# 8_RJ45_Connector.net
KiCad netlist of a schematic drawn in Altium Designer
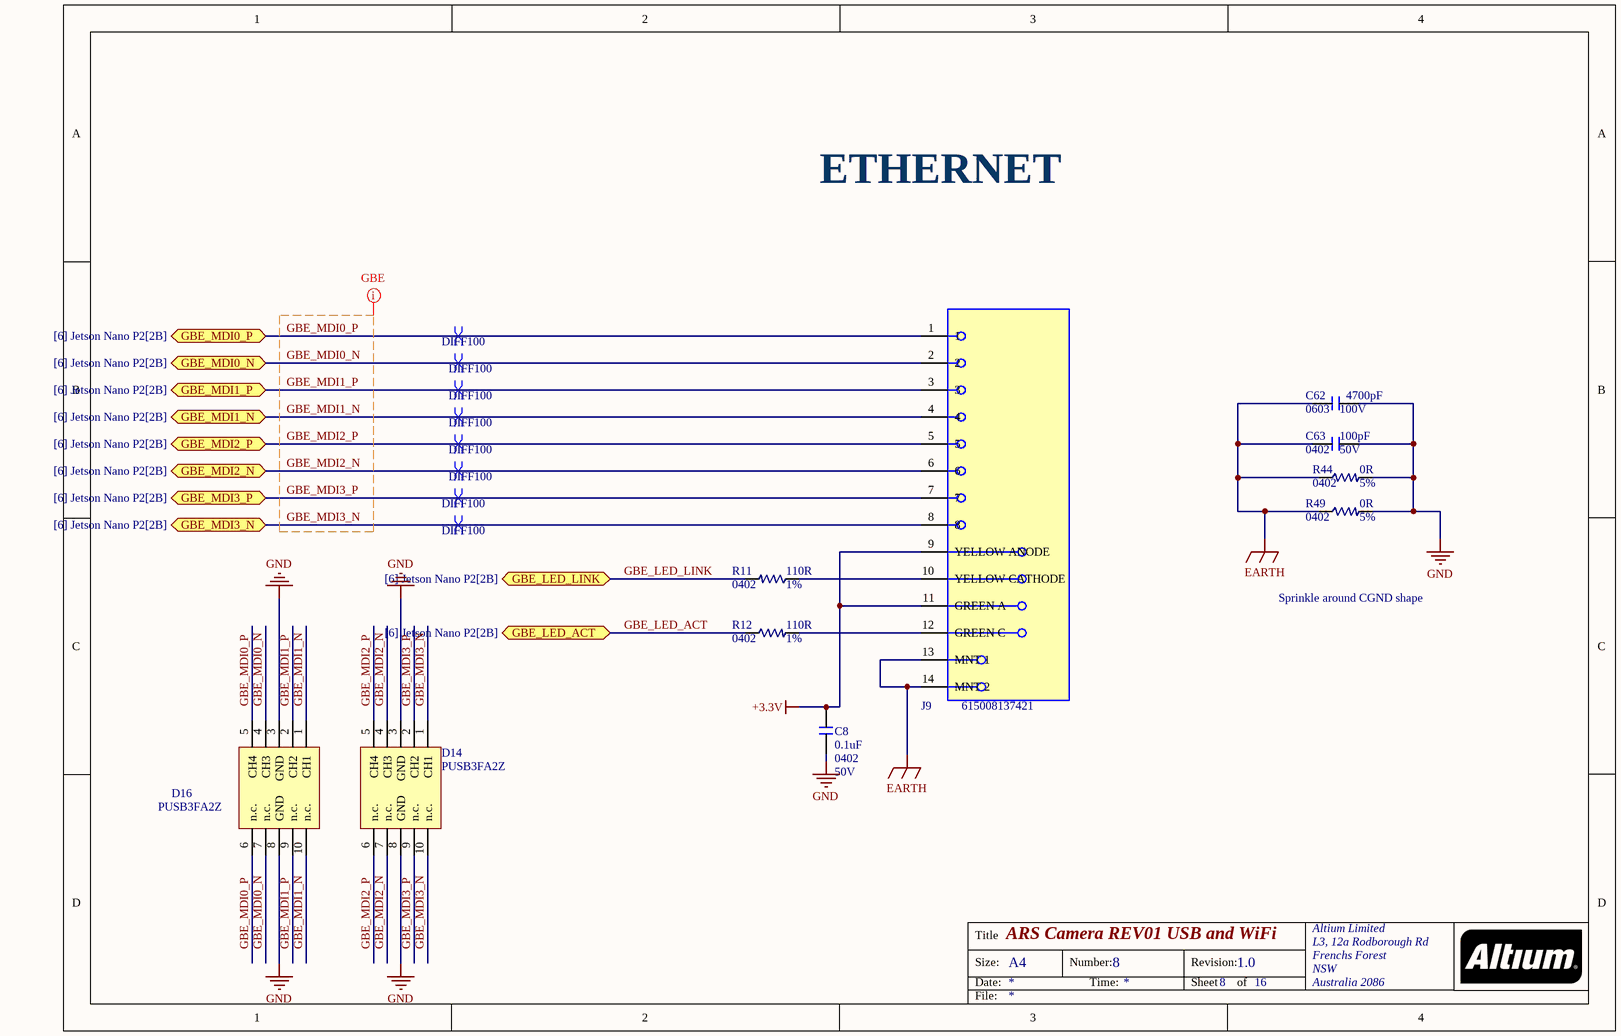
[diagram p0: [8] RJ45 Connector.SchDoc]

(export (version "E")
  (design (tool "Eeschema 10.0.6"))
  (components
    (comp (ref "C8")
      (value "0.1uF")
      (footprint "C0402M")
      (description "CAP CER 0.1UF 50V X7R 0402")
      (fields
        (field (name "MANUFACTURER") "Murata")
        (field (name "MANUFACTURER PART NUMBER") "GRM155R71H104KE14D")
        (field (name "CASE/PACKAGE") "0402")
        (field (name "VOLTAGE") "50V")
      )
      (libsource (lib "CommonLib") (part "CAP_CER"))
    )
    (comp (ref "C62")
      (value "4700pF")
      (footprint "C0603M")
      (description "CAP CER 4700PF 100V X7R 0603")
      (fields
        (field (name "CASE/PACKAGE") "0603")
        (field (name "TOLERANCE") "10%")
        (field (name "VOLTAGE RATING") "100V")
      )
      (libsource (lib "") (part "CAP_CER_1"))
    )
    (comp (ref "C63")
      (value "100pF")
      (footprint "C0402M")
      (description "CAP CER 100PF 50V C0G/NP0 0402")
      (fields
        (field (name "MANUFACTURER") "Murata")
        (field (name "MANUFACTURER PART NUMBER") "GRM1555C1H101JA01J")
        (field (name "CASE/PACKAGE") "0402")
        (field (name "VOLTAGE") "50V")
      )
      (libsource (lib "CommonLib") (part "CAP_CER"))
    )
    (comp (ref "D14")
      (value "PUSB3FA2Z")
      (footprint "SON50P100X50-10N")
      (description "ESD Suppressors / TVS Diodes PUSB3FA2 XSON10")
      (libsource (lib "Nauvus") (part "PUSB3FA2Z"))
    )
    (comp (ref "D16")
      (value "PUSB3FA2Z")
      (footprint "SON50P100X50-10N")
      (description "ESD Suppressors / TVS Diodes PUSB3FA2 XSON10")
      (libsource (lib "Nauvus") (part "PUSB3FA2Z"))
    )
    (comp (ref "J9")
      (value "615008137421")
      (footprint "Wurth_615008137421_MFG")
      (description "Modular Jack WR-MJ, Tab Up, Shielded, with LED and EMI Panel Finger, Horizontal Entry, THT, 8P8C")
      (libsource (lib "Schlib1") (part "615008137421"))
    )
    (comp (ref "R11")
      (value "110R")
      (footprint "R0402M")
      (description "RES SMD 110 OHM 1% 1/16W 0402")
      (fields (field (name "CASE CODE (IMPERIAL)") "0402") (field (name "TOLERANCE") "1%"))
      (libsource (lib "CommonLib") (part "RES_SMD"))
    )
    (comp (ref "R12")
      (value "110R")
      (footprint "R0402M")
      (description "RES SMD 110 OHM 1% 1/16W 0402")
      (fields (field (name "CASE CODE (IMPERIAL)") "0402") (field (name "TOLERANCE") "1%"))
      (libsource (lib "CommonLib") (part "RES_SMD"))
    )
    (comp (ref "R44")
      (value "0R")
      (footprint "R0402M")
      (description "YAGEO - RC0402JR-070RL. - RES, THICK FILM, 0R, 0.0625W, 0402")
      (fields
        (field (name "CASE/PACKAGE") "0402")
        (field (name "TOLERANCE") "5%")
        (field (name "RESISTANCE TOLERANCE") "5%")
      )
      (libsource (lib "CommonLib") (part "RES_SMD"))
    )
    (comp (ref "R49")
      (value "0R")
      (footprint "R0402M")
      (description "YAGEO - RC0402JR-070RL. - RES, THICK FILM, 0R, 0.0625W, 0402")
      (fields
        (field (name "CASE/PACKAGE") "0402")
        (field (name "TOLERANCE") "5%")
        (field (name "RESISTANCE TOLERANCE") "5%")
      )
      (libsource (lib "CommonLib") (part "RES_SMD"))
    )
  )
  (nets
    (net (code "1") (name "+3.3V") (class "Default")
      (node (ref "C8") (pin "2") (pinfunction "2_2") (pintype "passive"))
      (node (ref "J9") (pin "11") (pinfunction "GREEN_A_11") (pintype "passive"))
      (node (ref "J9") (pin "9") (pinfunction "YELLOW_ANODE_9") (pintype "passive"))
    )
    (net (code "2") (name "/GBE_LED_ACT") (class "Default")
      (node (ref "R12") (pin "2") (pinfunction "2_2") (pintype "passive"))
    )
    (net (code "3") (name "/GBE_LED_LINK") (class "Default")
      (node (ref "R11") (pin "1") (pinfunction "1_1") (pintype "passive"))
    )
    (net (code "4") (name "/GBE_MDI0_N") (class "Default")
      (node (ref "D16") (pin "4") (pinfunction "CH3_4") (pintype "passive"))
      (node (ref "D16") (pin "7") (pinfunction "n.c._7") (pintype "passive"))
      (node (ref "J9") (pin "2") (pinfunction "2_2") (pintype "passive"))
    )
    (net (code "5") (name "/GBE_MDI0_P") (class "Default")
      (node (ref "D16") (pin "5") (pinfunction "CH4_5") (pintype "passive"))
      (node (ref "D16") (pin "6") (pinfunction "n.c._6") (pintype "passive"))
      (node (ref "J9") (pin "1") (pinfunction "1_1") (pintype "passive"))
    )
    (net (code "6") (name "/GBE_MDI1_N") (class "Default")
      (node (ref "D16") (pin "1") (pinfunction "CH1_1") (pintype "passive"))
      (node (ref "D16") (pin "10") (pinfunction "n.c._10") (pintype "passive"))
      (node (ref "J9") (pin "4") (pinfunction "4_4") (pintype "passive"))
    )
    (net (code "7") (name "/GBE_MDI1_P") (class "Default")
      (node (ref "D16") (pin "2") (pinfunction "CH2_2") (pintype "passive"))
      (node (ref "D16") (pin "9") (pinfunction "n.c._9") (pintype "passive"))
      (node (ref "J9") (pin "3") (pinfunction "3_3") (pintype "passive"))
    )
    (net (code "8") (name "/GBE_MDI2_N") (class "Default")
      (node (ref "D14") (pin "4") (pinfunction "CH3_4") (pintype "passive"))
      (node (ref "D14") (pin "7") (pinfunction "n.c._7") (pintype "passive"))
      (node (ref "J9") (pin "6") (pinfunction "6_6") (pintype "passive"))
    )
    (net (code "9") (name "/GBE_MDI2_P") (class "Default")
      (node (ref "D14") (pin "5") (pinfunction "CH4_5") (pintype "passive"))
      (node (ref "D14") (pin "6") (pinfunction "n.c._6") (pintype "passive"))
      (node (ref "J9") (pin "5") (pinfunction "5_5") (pintype "passive"))
    )
    (net (code "10") (name "/GBE_MDI3_N") (class "Default")
      (node (ref "D14") (pin "1") (pinfunction "CH1_1") (pintype "passive"))
      (node (ref "D14") (pin "10") (pinfunction "n.c._10") (pintype "passive"))
      (node (ref "J9") (pin "8") (pinfunction "8_8") (pintype "passive"))
    )
    (net (code "11") (name "/GBE_MDI3_P") (class "Default")
      (node (ref "D14") (pin "2") (pinfunction "CH2_2") (pintype "passive"))
      (node (ref "D14") (pin "9") (pinfunction "n.c._9") (pintype "passive"))
      (node (ref "J9") (pin "7") (pinfunction "7_7") (pintype "passive"))
    )
    (net (code "12") (name "EARTH") (class "Default")
      (node (ref "C62") (pin "1") (pinfunction "1_1") (pintype "passive"))
      (node (ref "C63") (pin "2") (pinfunction "2_2") (pintype "passive"))
      (node (ref "J9") (pin "13") (pinfunction "MNT_1_13") (pintype "passive"))
      (node (ref "J9") (pin "14") (pinfunction "MNT_2_14") (pintype "passive"))
      (node (ref "R44") (pin "2") (pinfunction "2_2") (pintype "passive"))
      (node (ref "R49") (pin "2") (pinfunction "2_2") (pintype "passive"))
    )
    (net (code "13") (name "GND") (class "Default")
      (node (ref "C62") (pin "2") (pinfunction "2_2") (pintype "passive"))
      (node (ref "C63") (pin "1") (pinfunction "1_1") (pintype "passive"))
      (node (ref "C8") (pin "1") (pinfunction "1_1") (pintype "passive"))
      (node (ref "D14") (pin "3") (pinfunction "GND_3") (pintype "passive"))
      (node (ref "D14") (pin "8") (pinfunction "GND_8") (pintype "passive"))
      (node (ref "D16") (pin "3") (pinfunction "GND_3") (pintype "passive"))
      (node (ref "D16") (pin "8") (pinfunction "GND_8") (pintype "passive"))
      (node (ref "R44") (pin "1") (pinfunction "1_1") (pintype "passive"))
      (node (ref "R49") (pin "1") (pinfunction "1_1") (pintype "passive"))
    )
    (net (code "14") (name "Net-(J9-GREEN_C)") (class "Default")
      (node (ref "J9") (pin "12") (pinfunction "GREEN_C_12") (pintype "passive"))
      (node (ref "R12") (pin "1") (pinfunction "1_1") (pintype "passive"))
    )
    (net (code "15") (name "Net-(J9-YELLOW_CATHODE)") (class "Default")
      (node (ref "J9") (pin "10") (pinfunction "YELLOW_CATHODE_10") (pintype "passive"))
      (node (ref "R11") (pin "2") (pinfunction "2_2") (pintype "passive"))
    )
  )
)
